# motorModule-0_2.net
KiCad netlist of a schematic drawn in EAGLE
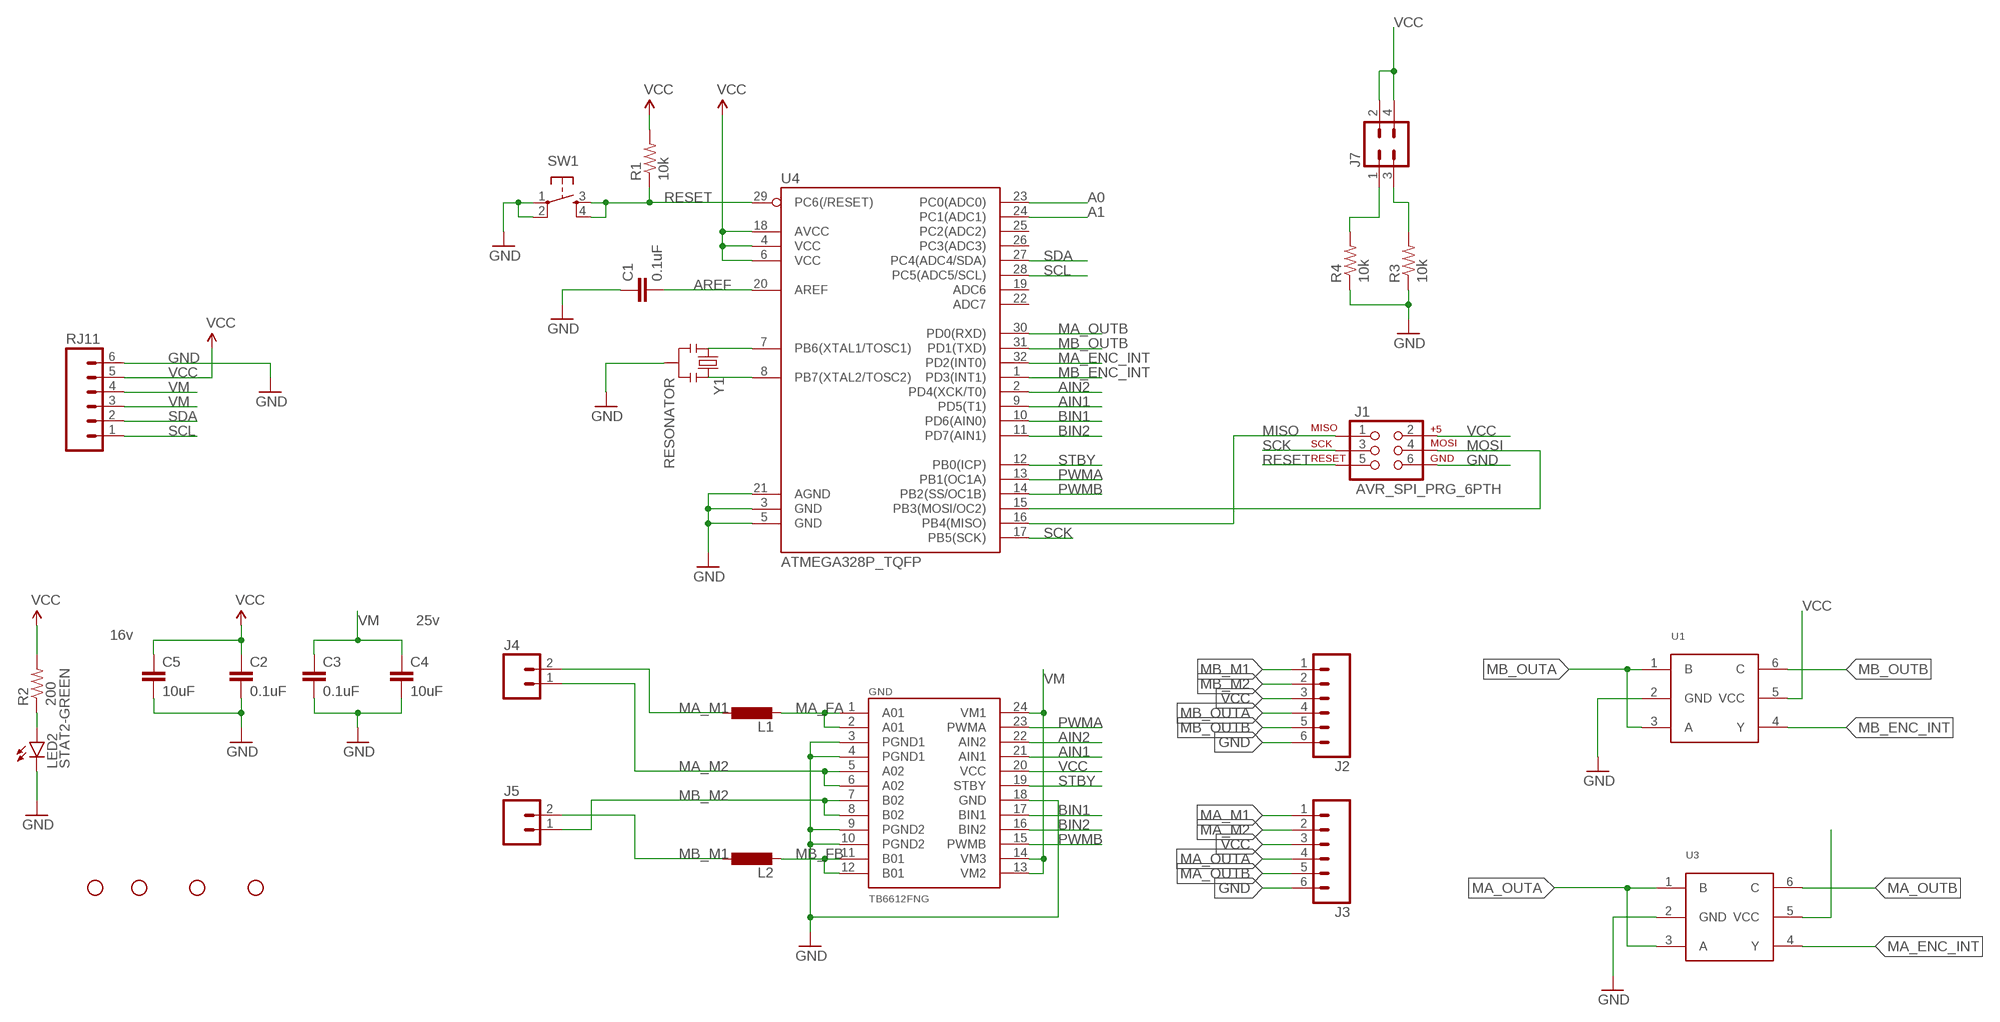
[diagram p0: schematic, sheet 1]

(export (version "E")
  (design (tool "Eeschema 10.0.6"))
  (components
    (comp (ref "C1")
      (value "0.1uF")
      (footprint "eagle-import:0603-CAP")
      (libsource (lib "eagle-import") (part "CAP0603-CAP"))
    )
    (comp (ref "C2")
      (value "0.1uF")
      (footprint "eagle-import:0603-CAP")
      (libsource (lib "eagle-import") (part "CAP0603-CAP"))
    )
    (comp (ref "C3")
      (value "0.1uF")
      (footprint "eagle-import:0603-CAP")
      (libsource (lib "eagle-import") (part "CAP0603-CAP"))
    )
    (comp (ref "C4")
      (value "10uF")
      (footprint "eagle-import:0805")
      (libsource (lib "eagle-import") (part "CAP0805"))
    )
    (comp (ref "C5")
      (value "10uF")
      (footprint "eagle-import:0805")
      (libsource (lib "eagle-import") (part "CAP0805"))
    )
    (comp (ref "GND")
      (value "TB6612FNG")
      (footprint "eagle-import:SSOP24")
      (libsource (lib "eagle-import") (part "TB6612FNG"))
    )
    (comp (ref "H1")
      (value "STAND-OFFPLATED")
      (footprint "eagle-import:STAND-OFF-PLATED")
      (libsource (lib "eagle-import") (part "STAND-OFFPLATED"))
    )
    (comp (ref "H2")
      (value "STAND-OFFPLATED")
      (footprint "eagle-import:STAND-OFF-PLATED")
      (libsource (lib "eagle-import") (part "STAND-OFFPLATED"))
    )
    (comp (ref "H3")
      (value "STAND-OFFPLATED")
      (footprint "eagle-import:STAND-OFF-PLATED")
      (libsource (lib "eagle-import") (part "STAND-OFFPLATED"))
    )
    (comp (ref "H4")
      (value "STAND-OFFPLATED")
      (footprint "eagle-import:STAND-OFF-PLATED")
      (libsource (lib "eagle-import") (part "STAND-OFFPLATED"))
    )
    (comp (ref "J1")
      (value "AVR_SPI_PRG_6PTH")
      (footprint "eagle-import:2X3")
      (libsource (lib "eagle-import") (part "AVR_SPI_PRG_6PTH"))
    )
    (comp (ref "J2")
      (value "M06JST-PH-6TH")
      (footprint "eagle-import:JST-PH-6-TH")
      (libsource (lib "eagle-import") (part "M06JST-PH-6TH"))
    )
    (comp (ref "J3")
      (value "M06JST-PH-6TH")
      (footprint "eagle-import:JST-PH-6-TH")
      (libsource (lib "eagle-import") (part "M06JST-PH-6TH"))
    )
    (comp (ref "J4")
      (value "M02JST-PTH-VERT")
      (footprint "eagle-import:JST-2-PTH-VERT")
      (libsource (lib "eagle-import") (part "M02JST-PTH-VERT"))
    )
    (comp (ref "J5")
      (value "M02JST-PTH-VERT")
      (footprint "eagle-import:JST-2-PTH-VERT")
      (libsource (lib "eagle-import") (part "M02JST-PTH-VERT"))
    )
    (comp (ref "J7")
      (value "M02X2")
      (footprint "eagle-import:2X2")
      (libsource (lib "eagle-import") (part "M02X2"))
    )
    (comp (ref "L1")
      (value "L-EUL1812")
      (footprint "eagle-import:L1812")
      (libsource (lib "eagle-import") (part "L-EUL1812"))
    )
    (comp (ref "L2")
      (value "L-EUL1812")
      (footprint "eagle-import:L1812")
      (libsource (lib "eagle-import") (part "L-EUL1812"))
    )
    (comp (ref "LED2")
      (value "STAT2-GREEN")
      (footprint "eagle-import:LED-0603")
      (libsource (lib "eagle-import") (part "LED0603"))
    )
    (comp (ref "R1")
      (value "10k")
      (footprint "eagle-import:0603-RES")
      (libsource (lib "eagle-import") (part "RESISTOR0603"))
    )
    (comp (ref "R2")
      (value "200")
      (footprint "eagle-import:0603-RES")
      (libsource (lib "eagle-import") (part "RESISTOR0603"))
    )
    (comp (ref "R3")
      (value "10k")
      (footprint "eagle-import:0603-RES")
      (libsource (lib "eagle-import") (part "RESISTOR0603"))
    )
    (comp (ref "R4")
      (value "10k")
      (footprint "eagle-import:0603-RES")
      (libsource (lib "eagle-import") (part "RESISTOR0603"))
    )
    (comp (ref "RJ11")
      (value "M06RJ11")
      (footprint "eagle-import:RJ11-6P6C")
      (libsource (lib "eagle-import") (part "M06RJ11"))
    )
    (comp (ref "SW1")
      (value "SWITCH_SPST_4_PINKMR2")
      (footprint "eagle-import:TACTILE_SWITCH_SMD-3")
      (libsource (lib "eagle-import") (part "SWITCH_SPST_4_PINKMR2"))
    )
    (comp (ref "U1")
      (value "74LVC1G58")
      (footprint "eagle-import:SOT363")
      (libsource (lib "eagle-import") (part "74LVC1G58"))
    )
    (comp (ref "U3")
      (value "74LVC1G58")
      (footprint "eagle-import:SOT363")
      (libsource (lib "eagle-import") (part "74LVC1G58"))
    )
    (comp (ref "U4")
      (value "ATMEGA328P_TQFP")
      (footprint "eagle-import:TQFP32-08")
      (libsource (lib "eagle-import") (part "ATMEGA328P_TQFP"))
    )
    (comp (ref "Y1")
      (value "RESONATOR")
      (footprint "eagle-import:RESONATOR-MURATA")
      (libsource (lib "eagle-import") (part "RESONATOR"))
    )
  )
  (nets
    (net (code "1") (name "/A0") (class "Default")
      (node (ref "J7") (pin "3") (pinfunction "3_3") (pintype "passive"))
      (node (ref "R3") (pin "2") (pinfunction "2_2") (pintype "passive"))
      (node (ref "U4") (pin "23") (pinfunction "PC0(ADC0)_23") (pintype "bidirectional"))
    )
    (net (code "2") (name "/A1") (class "Default")
      (node (ref "J7") (pin "1") (pinfunction "1_1") (pintype "passive"))
      (node (ref "R4") (pin "2") (pinfunction "2_2") (pintype "passive"))
      (node (ref "U4") (pin "24") (pinfunction "PC1(ADC1)_24") (pintype "bidirectional"))
    )
    (net (code "3") (name "/AIN1") (class "Default")
      (node (ref "GND") (pin "21") (pinfunction "AIN1_21") (pintype "bidirectional"))
      (node (ref "U4") (pin "9") (pinfunction "PD5(T1)_9") (pintype "bidirectional"))
    )
    (net (code "4") (name "/AIN2") (class "Default")
      (node (ref "GND") (pin "22") (pinfunction "AIN2_22") (pintype "bidirectional"))
      (node (ref "U4") (pin "2") (pinfunction "PD4(XCK/T0)_2") (pintype "bidirectional"))
    )
    (net (code "5") (name "/AREF") (class "Default")
      (node (ref "C1") (pin "2") (pinfunction "2_2") (pintype "passive"))
      (node (ref "U4") (pin "20") (pinfunction "AREF_20") (pintype "bidirectional"))
    )
    (net (code "6") (name "/BIN1") (class "Default")
      (node (ref "GND") (pin "17") (pinfunction "BIN1_17") (pintype "bidirectional"))
      (node (ref "U4") (pin "10") (pinfunction "PD6(AIN0)_10") (pintype "bidirectional"))
    )
    (net (code "7") (name "/BIN2") (class "Default")
      (node (ref "GND") (pin "16") (pinfunction "BIN2_16") (pintype "bidirectional"))
      (node (ref "U4") (pin "11") (pinfunction "PD7(AIN1)_11") (pintype "bidirectional"))
    )
    (net (code "8") (name "/MA_FA") (class "Default")
      (node (ref "GND") (pin "1") (pinfunction "A01_1") (pintype "bidirectional"))
      (node (ref "GND") (pin "2") (pinfunction "A01_2") (pintype "bidirectional"))
      (node (ref "L1") (pin "2") (pinfunction "2_2") (pintype "passive"))
    )
    (net (code "9") (name "/MB_FB") (class "Default")
      (node (ref "GND") (pin "11") (pinfunction "B01_11") (pintype "bidirectional"))
      (node (ref "GND") (pin "12") (pinfunction "B01_12") (pintype "bidirectional"))
      (node (ref "L2") (pin "2") (pinfunction "2_2") (pintype "passive"))
    )
    (net (code "10") (name "/MISO") (class "Default")
      (node (ref "J1") (pin "1") (pinfunction "1_1") (pintype "passive"))
      (node (ref "U4") (pin "16") (pinfunction "PB4(MISO)_16") (pintype "bidirectional"))
    )
    (net (code "11") (name "/MOSI") (class "Default")
      (node (ref "J1") (pin "4") (pinfunction "4_4") (pintype "passive"))
      (node (ref "U4") (pin "15") (pinfunction "PB3(MOSI/OC2)_15") (pintype "bidirectional"))
    )
    (net (code "12") (name "/PWMA") (class "Default")
      (node (ref "GND") (pin "23") (pinfunction "PWMA_23") (pintype "bidirectional"))
      (node (ref "U4") (pin "13") (pinfunction "PB1(OC1A)_13") (pintype "bidirectional"))
    )
    (net (code "13") (name "/PWMB") (class "Default")
      (node (ref "GND") (pin "15") (pinfunction "PWMB_15") (pintype "bidirectional"))
      (node (ref "U4") (pin "14") (pinfunction "PB2(SS/OC1B)_14") (pintype "bidirectional"))
    )
    (net (code "14") (name "/RESET") (class "Default")
      (node (ref "J1") (pin "5") (pinfunction "5_5") (pintype "passive"))
      (node (ref "R1") (pin "1") (pinfunction "1_1") (pintype "passive"))
      (node (ref "SW1") (pin "3") (pinfunction "3_3") (pintype "passive"))
      (node (ref "SW1") (pin "4") (pinfunction "4_4") (pintype "passive"))
      (node (ref "U4") (pin "29") (pinfunction "PC6(/RESET)_29") (pintype "bidirectional"))
    )
    (net (code "15") (name "/SCK") (class "Default")
      (node (ref "J1") (pin "3") (pinfunction "3_3") (pintype "passive"))
      (node (ref "U4") (pin "17") (pinfunction "PB5(SCK)_17") (pintype "bidirectional"))
    )
    (net (code "16") (name "/SCL") (class "Default")
      (node (ref "RJ11") (pin "1") (pinfunction "1_1") (pintype "passive"))
      (node (ref "U4") (pin "28") (pinfunction "PC5(ADC5/SCL)_28") (pintype "bidirectional"))
    )
    (net (code "17") (name "/SDA") (class "Default")
      (node (ref "RJ11") (pin "2") (pinfunction "2_2") (pintype "passive"))
      (node (ref "U4") (pin "27") (pinfunction "PC4(ADC4/SDA)_27") (pintype "bidirectional"))
    )
    (net (code "18") (name "/STBY") (class "Default")
      (node (ref "GND") (pin "19") (pinfunction "STBY_19") (pintype "bidirectional"))
      (node (ref "U4") (pin "12") (pinfunction "PB0(ICP)_12") (pintype "bidirectional"))
    )
    (net (code "19") (name "/VM") (class "Default")
      (node (ref "C3") (pin "1") (pinfunction "1_1") (pintype "passive"))
      (node (ref "C4") (pin "1") (pinfunction "1_1") (pintype "passive"))
      (node (ref "GND") (pin "13") (pinfunction "VM2_13") (pintype "bidirectional"))
      (node (ref "GND") (pin "14") (pinfunction "VM3_14") (pintype "bidirectional"))
      (node (ref "GND") (pin "24") (pinfunction "VM1_24") (pintype "bidirectional"))
      (node (ref "RJ11") (pin "3") (pinfunction "3_3") (pintype "passive"))
      (node (ref "RJ11") (pin "4") (pinfunction "4_4") (pintype "passive"))
    )
    (net (code "20") (name "GND") (class "Default")
      (node (ref "C1") (pin "1") (pinfunction "1_1") (pintype "passive"))
      (node (ref "C2") (pin "2") (pinfunction "2_2") (pintype "passive"))
      (node (ref "C3") (pin "2") (pinfunction "2_2") (pintype "passive"))
      (node (ref "C4") (pin "2") (pinfunction "2_2") (pintype "passive"))
      (node (ref "C5") (pin "2") (pinfunction "2_2") (pintype "passive"))
      (node (ref "GND") (pin "10") (pinfunction "PGND2_10") (pintype "bidirectional"))
      (node (ref "GND") (pin "18") (pinfunction "GND_18") (pintype "bidirectional"))
      (node (ref "GND") (pin "3") (pinfunction "PGND1_3") (pintype "bidirectional"))
      (node (ref "GND") (pin "4") (pinfunction "PGND1_4") (pintype "bidirectional"))
      (node (ref "GND") (pin "9") (pinfunction "PGND2_9") (pintype "bidirectional"))
      (node (ref "J1") (pin "6") (pinfunction "6_6") (pintype "passive"))
      (node (ref "J2") (pin "6") (pinfunction "6_6") (pintype "passive"))
      (node (ref "J3") (pin "6") (pinfunction "6_6") (pintype "passive"))
      (node (ref "LED2") (pin "C") (pinfunction "C_C") (pintype "passive"))
      (node (ref "R3") (pin "1") (pinfunction "1_1") (pintype "passive"))
      (node (ref "R4") (pin "1") (pinfunction "1_1") (pintype "passive"))
      (node (ref "RJ11") (pin "6") (pinfunction "6_6") (pintype "passive"))
      (node (ref "SW1") (pin "1") (pinfunction "1_1") (pintype "passive"))
      (node (ref "SW1") (pin "2") (pinfunction "2_2") (pintype "passive"))
      (node (ref "U1") (pin "2") (pinfunction "GND_2") (pintype "power_in"))
      (node (ref "U3") (pin "2") (pinfunction "GND_2") (pintype "power_in"))
      (node (ref "U4") (pin "21") (pinfunction "AGND_21") (pintype "bidirectional"))
      (node (ref "U4") (pin "3") (pinfunction "GND_3") (pintype "bidirectional"))
      (node (ref "U4") (pin "5") (pinfunction "GND_5") (pintype "bidirectional"))
      (node (ref "Y1") (pin "2") (pinfunction "2_2") (pintype "passive"))
    )
    (net (code "21") (name "MA_ENC_INT") (class "Default")
      (node (ref "U3") (pin "4") (pinfunction "Y_4") (pintype "bidirectional"))
      (node (ref "U4") (pin "32") (pinfunction "PD2(INT0)_32") (pintype "bidirectional"))
    )
    (net (code "22") (name "MA_M1") (class "Default")
      (node (ref "J3") (pin "1") (pinfunction "1_1") (pintype "passive"))
      (node (ref "J4") (pin "2") (pinfunction "2_2") (pintype "passive"))
      (node (ref "L1") (pin "1") (pinfunction "1_1") (pintype "passive"))
    )
    (net (code "23") (name "MA_M2") (class "Default")
      (node (ref "GND") (pin "5") (pinfunction "A02_5") (pintype "bidirectional"))
      (node (ref "GND") (pin "6") (pinfunction "A02_6") (pintype "bidirectional"))
      (node (ref "J3") (pin "2") (pinfunction "2_2") (pintype "passive"))
      (node (ref "J4") (pin "1") (pinfunction "1_1") (pintype "passive"))
    )
    (net (code "24") (name "MA_OUTA") (class "Default")
      (node (ref "J3") (pin "4") (pinfunction "4_4") (pintype "passive"))
      (node (ref "U3") (pin "1") (pinfunction "B_1") (pintype "bidirectional"))
      (node (ref "U3") (pin "3") (pinfunction "A_3") (pintype "bidirectional"))
    )
    (net (code "25") (name "MA_OUTB") (class "Default")
      (node (ref "J3") (pin "5") (pinfunction "5_5") (pintype "passive"))
      (node (ref "U3") (pin "6") (pinfunction "C_6") (pintype "bidirectional"))
      (node (ref "U4") (pin "30") (pinfunction "PD0(RXD)_30") (pintype "bidirectional"))
    )
    (net (code "26") (name "MB_ENC_INT") (class "Default")
      (node (ref "U1") (pin "4") (pinfunction "Y_4") (pintype "bidirectional"))
      (node (ref "U4") (pin "1") (pinfunction "PD3(INT1)_1") (pintype "bidirectional"))
    )
    (net (code "27") (name "MB_M1") (class "Default")
      (node (ref "J2") (pin "1") (pinfunction "1_1") (pintype "passive"))
      (node (ref "J5") (pin "2") (pinfunction "2_2") (pintype "passive"))
      (node (ref "L2") (pin "1") (pinfunction "1_1") (pintype "passive"))
    )
    (net (code "28") (name "MB_M2") (class "Default")
      (node (ref "GND") (pin "7") (pinfunction "B02_7") (pintype "bidirectional"))
      (node (ref "GND") (pin "8") (pinfunction "B02_8") (pintype "bidirectional"))
      (node (ref "J2") (pin "2") (pinfunction "2_2") (pintype "passive"))
      (node (ref "J5") (pin "1") (pinfunction "1_1") (pintype "passive"))
    )
    (net (code "29") (name "MB_OUTA") (class "Default")
      (node (ref "J2") (pin "4") (pinfunction "4_4") (pintype "passive"))
      (node (ref "U1") (pin "1") (pinfunction "B_1") (pintype "bidirectional"))
      (node (ref "U1") (pin "3") (pinfunction "A_3") (pintype "bidirectional"))
    )
    (net (code "30") (name "MB_OUTB") (class "Default")
      (node (ref "J2") (pin "5") (pinfunction "5_5") (pintype "passive"))
      (node (ref "U1") (pin "6") (pinfunction "C_6") (pintype "bidirectional"))
      (node (ref "U4") (pin "31") (pinfunction "PD1(TXD)_31") (pintype "bidirectional"))
    )
    (net (code "31") (name "Net-(LED2-PadA)") (class "Default")
      (node (ref "LED2") (pin "A") (pinfunction "A_A") (pintype "passive"))
      (node (ref "R2") (pin "1") (pinfunction "1_1") (pintype "passive"))
    )
    (net (code "32") (name "Net-(U4-PB6(XTAL1{slash}TOSC1))") (class "Default")
      (node (ref "U4") (pin "7") (pinfunction "PB6(XTAL1/TOSC1)_7") (pintype "bidirectional"))
      (node (ref "Y1") (pin "1") (pinfunction "1_1") (pintype "passive"))
    )
    (net (code "33") (name "Net-(U4-PB7(XTAL2{slash}TOSC2))") (class "Default")
      (node (ref "U4") (pin "8") (pinfunction "PB7(XTAL2/TOSC2)_8") (pintype "bidirectional"))
      (node (ref "Y1") (pin "3") (pinfunction "3_3") (pintype "passive"))
    )
    (net (code "34") (name "VCC") (class "Default")
      (node (ref "C2") (pin "1") (pinfunction "1_1") (pintype "passive"))
      (node (ref "C5") (pin "1") (pinfunction "1_1") (pintype "passive"))
      (node (ref "GND") (pin "20") (pinfunction "VCC_20") (pintype "bidirectional"))
      (node (ref "J1") (pin "2") (pinfunction "2_2") (pintype "passive"))
      (node (ref "J2") (pin "3") (pinfunction "3_3") (pintype "passive"))
      (node (ref "J3") (pin "3") (pinfunction "3_3") (pintype "passive"))
      (node (ref "J7") (pin "2") (pinfunction "2_2") (pintype "passive"))
      (node (ref "J7") (pin "4") (pinfunction "4_4") (pintype "passive"))
      (node (ref "R1") (pin "2") (pinfunction "2_2") (pintype "passive"))
      (node (ref "R2") (pin "2") (pinfunction "2_2") (pintype "passive"))
      (node (ref "RJ11") (pin "5") (pinfunction "5_5") (pintype "passive"))
      (node (ref "U1") (pin "5") (pinfunction "VCC_5") (pintype "power_in"))
      (node (ref "U3") (pin "5") (pinfunction "VCC_5") (pintype "power_in"))
      (node (ref "U4") (pin "18") (pinfunction "AVCC_18") (pintype "bidirectional"))
      (node (ref "U4") (pin "4") (pinfunction "VCC_4") (pintype "bidirectional"))
      (node (ref "U4") (pin "6") (pinfunction "VCC_6") (pintype "bidirectional"))
    )
    (net (code "35") (name "unconnected-(U4-ADC6-Pad19)") (class "Default")
      (node (ref "U4") (pin "19") (pinfunction "ADC6_19") (pintype "bidirectional"))
    )
    (net (code "36") (name "unconnected-(U4-ADC7-Pad22)") (class "Default")
      (node (ref "U4") (pin "22") (pinfunction "ADC7_22") (pintype "bidirectional"))
    )
    (net (code "37") (name "unconnected-(U4-PC2(ADC2)-Pad25)") (class "Default")
      (node (ref "U4") (pin "25") (pinfunction "PC2(ADC2)_25") (pintype "bidirectional"))
    )
    (net (code "38") (name "unconnected-(U4-PC3(ADC3)-Pad26)") (class "Default")
      (node (ref "U4") (pin "26") (pinfunction "PC3(ADC3)_26") (pintype "bidirectional"))
    )
  )
)
